# Sparkfun_AS6212_Qwiic.net
KiCad netlist of a schematic drawn in EAGLE
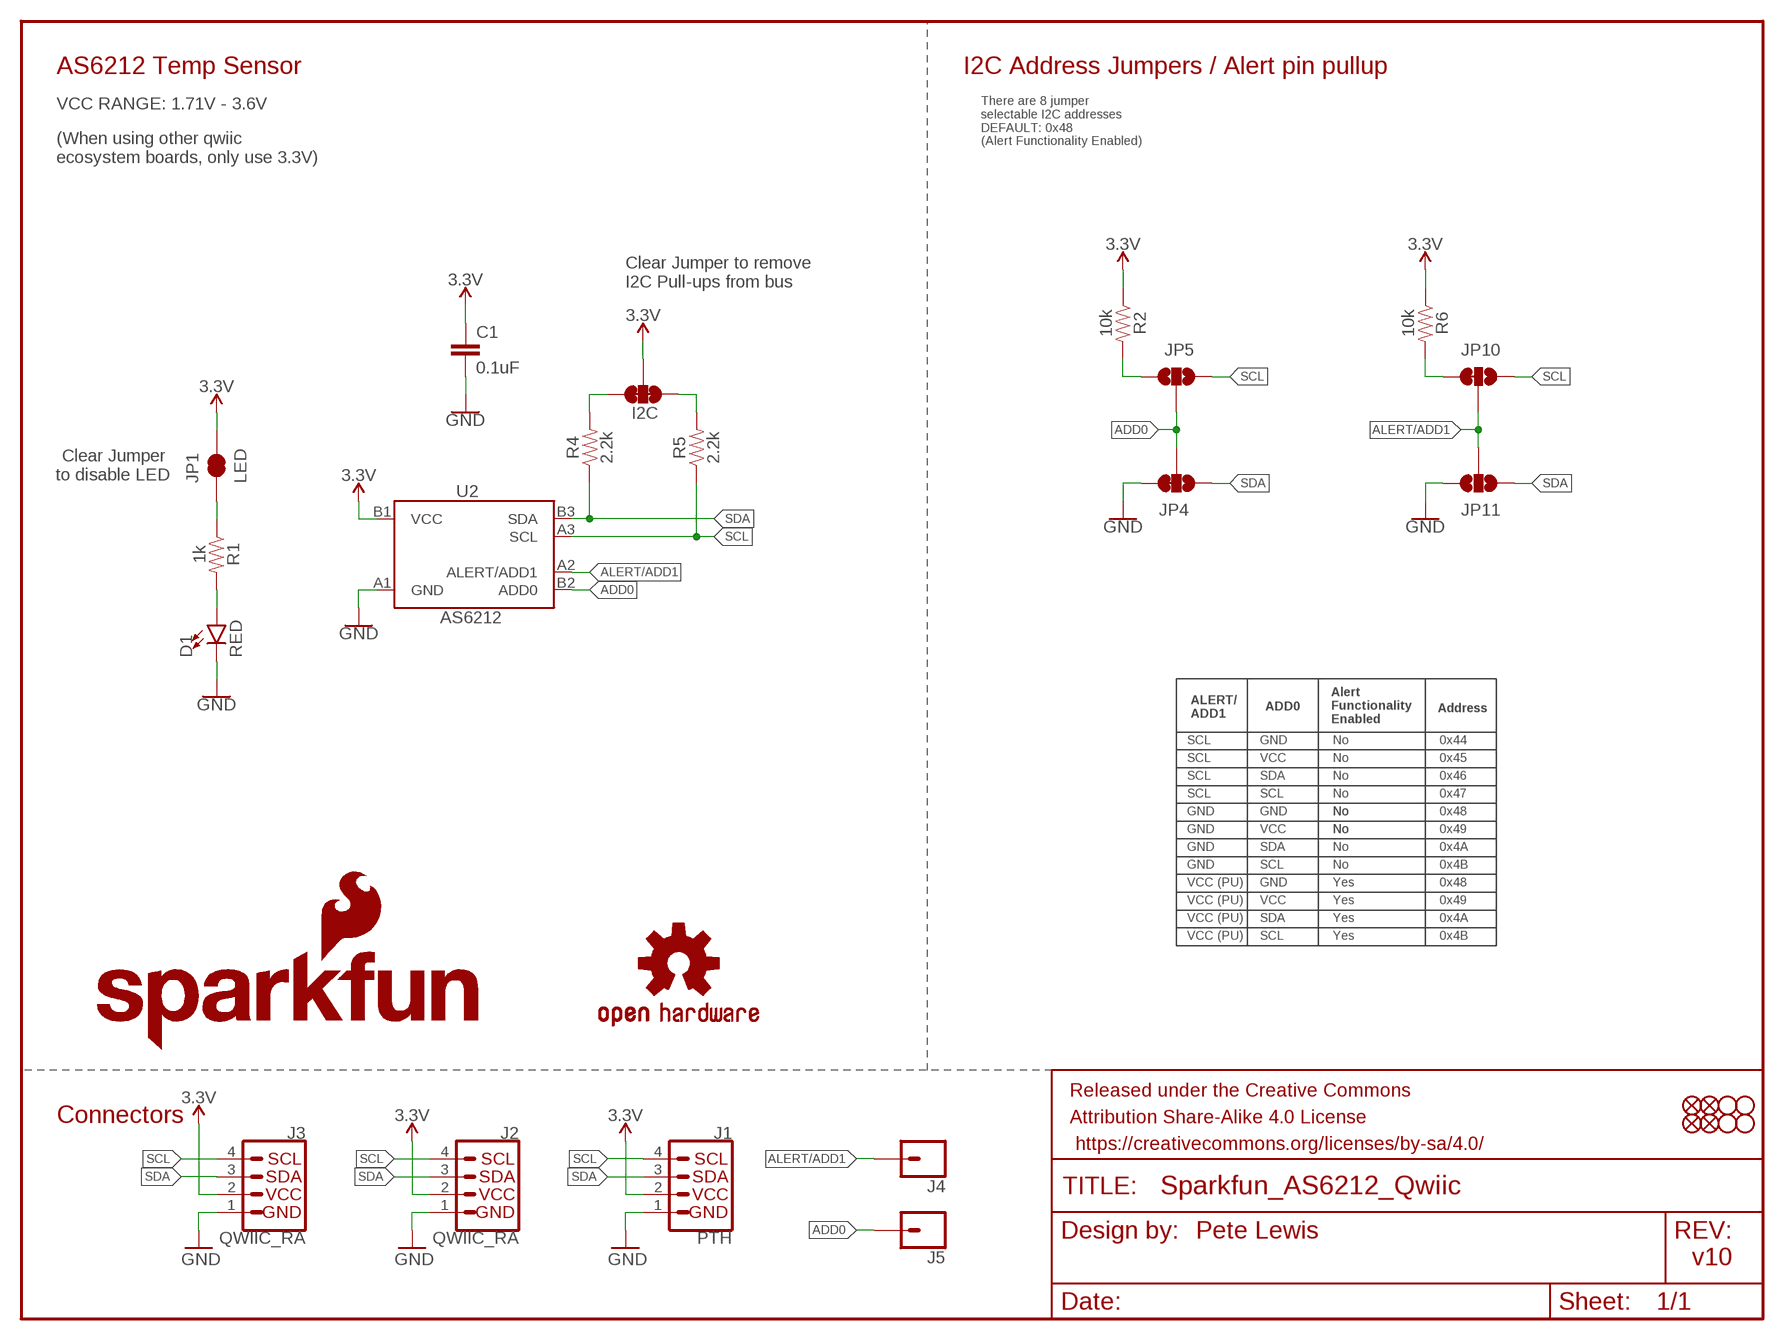
[diagram p0: schematic, sheet 1]

(export (version "E")
  (design (tool "Eeschema 10.0.6"))
  (components
    (comp (ref "C1")
      (value "0.1uF")
      (footprint "eagle-import:0603")
      (libsource (lib "eagle-import") (part "0.1UF-0603-25V-(+80/-20%)"))
    )
    (comp (ref "D1")
      (value "RED")
      (footprint "eagle-import:LED-0603")
      (libsource (lib "eagle-import") (part "LED-RED0603"))
    )
    (comp (ref "FD1")
      (value "FIDUCIALUFIDUCIAL")
      (footprint "eagle-import:FIDUCIAL-MICRO")
      (libsource (lib "eagle-import") (part "FIDUCIALUFIDUCIAL"))
    )
    (comp (ref "FD2")
      (value "FIDUCIALUFIDUCIAL")
      (footprint "eagle-import:FIDUCIAL-MICRO")
      (libsource (lib "eagle-import") (part "FIDUCIALUFIDUCIAL"))
    )
    (comp (ref "FD3")
      (value "FIDUCIALUFIDUCIAL")
      (footprint "eagle-import:FIDUCIAL-MICRO")
      (libsource (lib "eagle-import") (part "FIDUCIALUFIDUCIAL"))
    )
    (comp (ref "FD4")
      (value "FIDUCIALUFIDUCIAL")
      (footprint "eagle-import:FIDUCIAL-MICRO")
      (libsource (lib "eagle-import") (part "FIDUCIALUFIDUCIAL"))
    )
    (comp (ref "FRAME1")
      (value "FRAME-LETTER")
      (footprint "eagle-import:CREATIVE_COMMONS")
      (libsource (lib "eagle-import") (part "FRAME-LETTER"))
    )
    (comp (ref "I2C")
      (value "JUMPER-SMT_3_2-NC_TRACE_SILK")
      (footprint "eagle-import:SMT-JUMPER_3_2-NC_TRACE_SILK")
      (libsource (lib "eagle-import") (part "JUMPER-SMT_3_2-NC_TRACE_SILK"))
    )
    (comp (ref "J1")
      (value "PTH")
      (footprint "eagle-import:1X04_NO_SILK")
      (libsource (lib "eagle-import") (part "I2C_STANDARD_NO_SILK"))
    )
    (comp (ref "J2")
      (value "QWIIC_RA")
      (footprint "eagle-import:JST04_1MM_RA")
      (libsource (lib "eagle-import") (part "QWIIC_CONNECTORJS-1MM"))
    )
    (comp (ref "J3")
      (value "QWIIC_RA")
      (footprint "eagle-import:JST04_1MM_RA")
      (libsource (lib "eagle-import") (part "QWIIC_CONNECTORJS-1MM"))
    )
    (comp (ref "J4")
      (value "CONN_01PTH_NO_SILK_YES_STOP")
      (footprint "eagle-import:1X01_NO_SILK")
      (libsource (lib "eagle-import") (part "CONN_01PTH_NO_SILK_YES_STOP"))
    )
    (comp (ref "J5")
      (value "CONN_01PTH_NO_SILK_YES_STOP")
      (footprint "eagle-import:1X01_NO_SILK")
      (libsource (lib "eagle-import") (part "CONN_01PTH_NO_SILK_YES_STOP"))
    )
    (comp (ref "JP1")
      (value "LED")
      (footprint "eagle-import:SMT-JUMPER_2_NC_TRACE_SILK")
      (libsource (lib "eagle-import") (part "JUMPER-SMT_2_NC_TRACE_SILK"))
    )
    (comp (ref "JP2")
      (value "STAND-OFF")
      (footprint "eagle-import:STAND-OFF")
      (libsource (lib "eagle-import") (part "STAND-OFF"))
    )
    (comp (ref "JP3")
      (value "STAND-OFF")
      (footprint "eagle-import:STAND-OFF")
      (libsource (lib "eagle-import") (part "STAND-OFF"))
    )
    (comp (ref "JP4")
      (value "JUMPER-SMT_3_1-NC_TRACE_NO-SILK")
      (footprint "eagle-import:SMT-JUMPER_3_1-NC_TRACE_NO-SILK")
      (libsource (lib "eagle-import") (part "JUMPER-SMT_3_1-NC_TRACE_NO-SILK"))
    )
    (comp (ref "JP5")
      (value "JUMPER-SMT_3_NO_NO_SILK")
      (footprint "eagle-import:SMT-JUMPER_3_0-NO_TRACE_NO-SILK")
      (libsource (lib "eagle-import") (part "JUMPER-SMT_3_NO_NO_SILK"))
    )
    (comp (ref "JP8")
      (value "STAND-OFF")
      (footprint "eagle-import:STAND-OFF")
      (libsource (lib "eagle-import") (part "STAND-OFF"))
    )
    (comp (ref "JP9")
      (value "STAND-OFF")
      (footprint "eagle-import:STAND-OFF")
      (libsource (lib "eagle-import") (part "STAND-OFF"))
    )
    (comp (ref "JP10")
      (value "JUMPER-SMT_3_1-NC_TRACE_NO-SILK")
      (footprint "eagle-import:SMT-JUMPER_3_1-NC_TRACE_NO-SILK")
      (libsource (lib "eagle-import") (part "JUMPER-SMT_3_1-NC_TRACE_NO-SILK"))
    )
    (comp (ref "JP11")
      (value "JUMPER-SMT_3_NO_NO_SILK")
      (footprint "eagle-import:SMT-JUMPER_3_0-NO_TRACE_NO-SILK")
      (libsource (lib "eagle-import") (part "JUMPER-SMT_3_NO_NO_SILK"))
    )
    (comp (ref "LOGO1")
      (value "OSHW-LOGOMINI")
      (footprint "eagle-import:OSHW-LOGO-MINI")
      (libsource (lib "eagle-import") (part "OSHW-LOGOMINI"))
    )
    (comp (ref "LOGO4")
      (value "SFE_LOGO_NAME_FLAME.1_INCH")
      (footprint "eagle-import:SFE_LOGO_NAME_FLAME_.1")
      (libsource (lib "eagle-import") (part "SFE_LOGO_NAME_FLAME.1_INCH"))
    )
    (comp (ref "R1")
      (value "1k")
      (footprint "eagle-import:0603")
      (libsource (lib "eagle-import") (part "1KOHM-0603-1/10W-1%"))
    )
    (comp (ref "R2")
      (value "10k")
      (footprint "eagle-import:0603")
      (libsource (lib "eagle-import") (part "10KOHM-0603-1/10W-1%"))
    )
    (comp (ref "R4")
      (value "2.2k")
      (footprint "eagle-import:0603")
      (libsource (lib "eagle-import") (part "2.2KOHM-0603-1/10W-1%"))
    )
    (comp (ref "R5")
      (value "2.2k")
      (footprint "eagle-import:0603")
      (libsource (lib "eagle-import") (part "2.2KOHM-0603-1/10W-1%"))
    )
    (comp (ref "R6")
      (value "10k")
      (footprint "eagle-import:0603")
      (libsource (lib "eagle-import") (part "10KOHM-0603-1/10W-1%"))
    )
    (comp (ref "U2")
      (value "AS6212")
      (footprint "eagle-import:WLCSP")
      (libsource (lib "eagle-import") (part "AS6212WLCSP"))
    )
  )
  (nets
    (net (code "1") (name "3.3V") (class "Default")
      (node (ref "C1") (pin "1") (pinfunction "1_1") (pintype "passive"))
      (node (ref "I2C") (pin "2") (pinfunction "2_2") (pintype "passive"))
      (node (ref "J1") (pin "2") (pinfunction "2_2") (pintype "power_in"))
      (node (ref "J2") (pin "2") (pinfunction "2_2") (pintype "power_in"))
      (node (ref "J3") (pin "2") (pinfunction "2_2") (pintype "power_in"))
      (node (ref "JP1") (pin "2") (pinfunction "2_2") (pintype "passive"))
      (node (ref "R2") (pin "1") (pinfunction "1_1") (pintype "passive"))
      (node (ref "R6") (pin "1") (pinfunction "1_1") (pintype "passive"))
      (node (ref "U2") (pin "B1") (pinfunction "VCC_B1") (pintype "bidirectional"))
    )
    (net (code "2") (name "ADD0") (class "Default")
      (node (ref "J5") (pin "1") (pinfunction "1_1") (pintype "passive"))
      (node (ref "JP4") (pin "2") (pinfunction "2_2") (pintype "passive"))
      (node (ref "JP5") (pin "2") (pinfunction "2_2") (pintype "passive"))
      (node (ref "U2") (pin "B2") (pinfunction "ADD0_B2") (pintype "bidirectional"))
    )
    (net (code "3") (name "ALERT{slash}ADD1") (class "Default")
      (node (ref "J4") (pin "1") (pinfunction "1_1") (pintype "passive"))
      (node (ref "JP10") (pin "2") (pinfunction "2_2") (pintype "passive"))
      (node (ref "JP11") (pin "2") (pinfunction "2_2") (pintype "passive"))
      (node (ref "U2") (pin "A2") (pinfunction "ALERT/ADD1_A2") (pintype "bidirectional"))
    )
    (net (code "4") (name "GND") (class "Default")
      (node (ref "C1") (pin "2") (pinfunction "2_2") (pintype "passive"))
      (node (ref "D1") (pin "C") (pinfunction "C_C") (pintype "passive"))
      (node (ref "J1") (pin "1") (pinfunction "1_1") (pintype "power_in"))
      (node (ref "J2") (pin "1") (pinfunction "1_1") (pintype "power_in"))
      (node (ref "J3") (pin "1") (pinfunction "1_1") (pintype "power_in"))
      (node (ref "JP11") (pin "3") (pinfunction "3_3") (pintype "passive"))
      (node (ref "JP4") (pin "3") (pinfunction "3_3") (pintype "passive"))
      (node (ref "U2") (pin "A1") (pinfunction "GND_A1") (pintype "bidirectional"))
    )
    (net (code "5") (name "Net-(D1-PadA)") (class "Default")
      (node (ref "D1") (pin "A") (pinfunction "A_A") (pintype "passive"))
      (node (ref "R1") (pin "2") (pinfunction "2_2") (pintype "passive"))
    )
    (net (code "6") (name "Net-(I2C-Pad1)") (class "Default")
      (node (ref "I2C") (pin "1") (pinfunction "1_1") (pintype "passive"))
      (node (ref "R5") (pin "2") (pinfunction "2_2") (pintype "passive"))
    )
    (net (code "7") (name "Net-(I2C-Pad3)") (class "Default")
      (node (ref "I2C") (pin "3") (pinfunction "3_3") (pintype "passive"))
      (node (ref "R4") (pin "2") (pinfunction "2_2") (pintype "passive"))
    )
    (net (code "8") (name "Net-(JP1-Pad1)") (class "Default")
      (node (ref "JP1") (pin "1") (pinfunction "1_1") (pintype "passive"))
      (node (ref "R1") (pin "1") (pinfunction "1_1") (pintype "passive"))
    )
    (net (code "9") (name "Net-(JP5-Pad1)") (class "Default")
      (node (ref "JP5") (pin "1") (pinfunction "1_1") (pintype "passive"))
      (node (ref "R2") (pin "2") (pinfunction "2_2") (pintype "passive"))
    )
    (net (code "10") (name "Net-(JP10-Pad3)") (class "Default")
      (node (ref "JP10") (pin "3") (pinfunction "3_3") (pintype "passive"))
      (node (ref "R6") (pin "2") (pinfunction "2_2") (pintype "passive"))
    )
    (net (code "11") (name "SCL") (class "Default")
      (node (ref "J1") (pin "4") (pinfunction "4_4") (pintype "passive"))
      (node (ref "J2") (pin "4") (pinfunction "4_4") (pintype "passive"))
      (node (ref "J3") (pin "4") (pinfunction "4_4") (pintype "passive"))
      (node (ref "JP10") (pin "1") (pinfunction "1_1") (pintype "passive"))
      (node (ref "JP5") (pin "3") (pinfunction "3_3") (pintype "passive"))
      (node (ref "R5") (pin "1") (pinfunction "1_1") (pintype "passive"))
      (node (ref "U2") (pin "A3") (pinfunction "SCL_A3") (pintype "bidirectional"))
    )
    (net (code "12") (name "SDA") (class "Default")
      (node (ref "J1") (pin "3") (pinfunction "3_3") (pintype "passive"))
      (node (ref "J2") (pin "3") (pinfunction "3_3") (pintype "passive"))
      (node (ref "J3") (pin "3") (pinfunction "3_3") (pintype "passive"))
      (node (ref "JP11") (pin "1") (pinfunction "1_1") (pintype "passive"))
      (node (ref "JP4") (pin "1") (pinfunction "1_1") (pintype "passive"))
      (node (ref "R4") (pin "1") (pinfunction "1_1") (pintype "passive"))
      (node (ref "U2") (pin "B3") (pinfunction "SDA_B3") (pintype "bidirectional"))
    )
  )
)
